# untitled.net
KiCad netlist of a schematic drawn in EAGLE
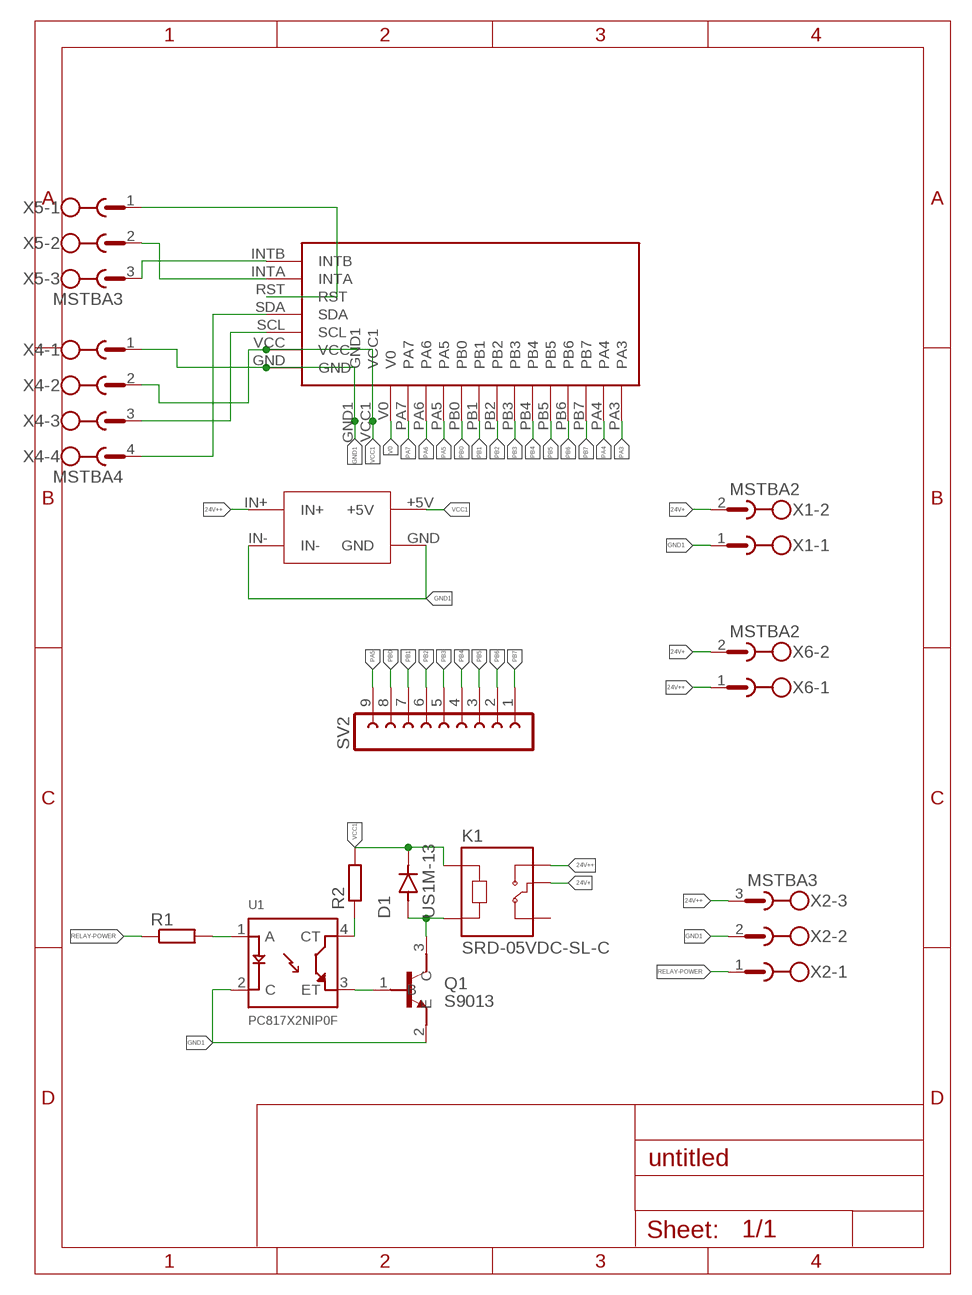
[diagram p0: schematic, sheet 1]

(export (version "E")
  (design (tool "Eeschema 10.0.6"))
  (components
    (comp (ref "D1")
      (value "US1M-13")
      (footprint "eagle-import:DIOM5226X240N")
      (fields (field (name "MF") "Diodes Incorporated"))
      (libsource (lib "eagle-import") (part "US1M-13"))
    )
    (comp (ref "K1")
      (value "SRD-05VDC-SL-C")
      (footprint "eagle-import:RELAY_SRD-05VDC-SL-C")
      (fields (field (name "MF") "Songle Relay"))
      (libsource (lib "eagle-import") (part "SRD-05VDC-SL-C"))
    )
    (comp (ref "MCP23017-I2C1")
      (value "MCP23017-I2C")
      (footprint "eagle-import:MCP23017-I2C")
      (libsource (lib "eagle-import") (part "MCP23017-I2C"))
    )
    (comp (ref "Q1")
      (value "S9013")
      (footprint "eagle-import:SOT95P240X120-3N")
      (fields (field (name "MF") "JCET"))
      (libsource (lib "eagle-import") (part "S9013"))
    )
    (comp (ref "R1")
      (value "R-EU_R0805")
      (footprint "eagle-import:R0805")
      (libsource (lib "eagle-import") (part "R-EU_R0805"))
    )
    (comp (ref "R2")
      (value "R-EU_R0805")
      (footprint "eagle-import:R0805")
      (libsource (lib "eagle-import") (part "R-EU_R0805"))
    )
    (comp (ref "SUPER-STEPDOWN1")
      (value "SUPER-STEPDOWN")
      (footprint "eagle-import:SUPER-STEPDOWN")
      (libsource (lib "eagle-import") (part "SUPER-STEPDOWN"))
    )
    (comp (ref "SV2")
      (value "FE09-1")
      (footprint "eagle-import:FE09")
      (libsource (lib "eagle-import") (part "FE09-1"))
    )
    (comp (ref "U1")
      (value "PC817X2NIP0F")
      (footprint "eagle-import:SOT254P975X400-4N")
      (fields (field (name "MF") "Sharp Microelectronics"))
      (libsource (lib "eagle-import") (part "PC817X2NIP0F"))
    )
    (comp (ref "X1")
      (value "MSTBA2")
      (footprint "eagle-import:MSTBA2")
      (fields (field (name "MF") "FARNELL") (field (name "MPN") "1757242"))
      (libsource (lib "eagle-import") (part "MSTBA2"))
    )
    (comp (ref "X2")
      (value "MSTBA3")
      (footprint "eagle-import:MSTBA3")
      (fields (field (name "MF") "FARNELL") (field (name "MPN") "1757255"))
      (libsource (lib "eagle-import") (part "MSTBA3"))
    )
    (comp (ref "X4")
      (value "MSTBA4")
      (footprint "eagle-import:MSTBA4")
      (fields (field (name "MF") "FARNELL") (field (name "MPN") "1757268"))
      (libsource (lib "eagle-import") (part "MSTBA4"))
    )
    (comp (ref "X5")
      (value "MSTBA3")
      (footprint "eagle-import:MSTBA3")
      (fields (field (name "MF") "FARNELL") (field (name "MPN") "1757255"))
      (libsource (lib "eagle-import") (part "MSTBA3"))
    )
    (comp (ref "X6")
      (value "MSTBA2")
      (footprint "eagle-import:MSTBA2")
      (fields (field (name "MF") "FARNELL") (field (name "MPN") "1757242"))
      (libsource (lib "eagle-import") (part "MSTBA2"))
    )
  )
  (nets
    (net (code "1") (name "24V+") (class "Default")
      (node (ref "K1") (pin "COM") (pinfunction "COM_COM") (pintype "passive"))
      (node (ref "X1") (pin "2") (pinfunction "1_2") (pintype "passive"))
      (node (ref "X6") (pin "2") (pinfunction "1_2") (pintype "passive"))
    )
    (net (code "2") (name "24V++") (class "Default")
      (node (ref "K1") (pin "NO") (pinfunction "NO_NO") (pintype "passive"))
      (node (ref "SUPER-STEPDOWN1") (pin "IN+") (pinfunction "IN+_IN+") (pintype "bidirectional"))
      (node (ref "X2") (pin "3") (pinfunction "1_3") (pintype "passive"))
      (node (ref "X6") (pin "1") (pinfunction "1_1") (pintype "passive"))
    )
    (net (code "3") (name "GND1") (class "Default")
      (node (ref "MCP23017-I2C1") (pin "GND") (pinfunction "GND_GND") (pintype "bidirectional"))
      (node (ref "MCP23017-I2C1") (pin "GND1") (pinfunction "GND1_GND1") (pintype "bidirectional"))
      (node (ref "Q1") (pin "2") (pinfunction "E_2") (pintype "passive"))
      (node (ref "SUPER-STEPDOWN1") (pin "GND") (pinfunction "GND_GND") (pintype "bidirectional"))
      (node (ref "SUPER-STEPDOWN1") (pin "IN-") (pinfunction "IN-_IN-") (pintype "bidirectional"))
      (node (ref "U1") (pin "2") (pinfunction "C_2") (pintype "passive"))
      (node (ref "X1") (pin "1") (pinfunction "1_1") (pintype "passive"))
      (node (ref "X2") (pin "2") (pinfunction "1_2") (pintype "passive"))
      (node (ref "X4") (pin "1") (pinfunction "1_1") (pintype "passive"))
    )
    (net (code "4") (name "Net-(MCP23017-I2C1-PadRST)") (class "Default")
      (node (ref "MCP23017-I2C1") (pin "RST") (pinfunction "RST_RST") (pintype "bidirectional"))
      (node (ref "X5") (pin "1") (pinfunction "1_1") (pintype "passive"))
    )
    (net (code "5") (name "Net-(Q1-B)") (class "Default")
      (node (ref "Q1") (pin "1") (pinfunction "B_1") (pintype "passive"))
      (node (ref "U1") (pin "3") (pinfunction "ET_3") (pintype "passive"))
    )
    (net (code "6") (name "Net-(Q1-C)") (class "Default")
      (node (ref "D1") (pin "A") (pinfunction "A_A") (pintype "passive"))
      (node (ref "K1") (pin "A2") (pinfunction "A2_A2") (pintype "passive"))
      (node (ref "Q1") (pin "3") (pinfunction "C_3") (pintype "passive"))
    )
    (net (code "7") (name "Net-(U1-A)") (class "Default")
      (node (ref "R1") (pin "2") (pinfunction "2_2") (pintype "passive"))
      (node (ref "U1") (pin "1") (pinfunction "A_1") (pintype "passive"))
    )
    (net (code "8") (name "Net-(U1-CT)") (class "Default")
      (node (ref "R2") (pin "1") (pinfunction "1_1") (pintype "passive"))
      (node (ref "U1") (pin "4") (pinfunction "CT_4") (pintype "passive"))
    )
    (net (code "9") (name "Net-(X4C-1)") (class "Default")
      (node (ref "MCP23017-I2C1") (pin "SCL") (pinfunction "SCL_SCL") (pintype "bidirectional"))
      (node (ref "X4") (pin "3") (pinfunction "1_3") (pintype "passive"))
    )
    (net (code "10") (name "Net-(X4D-1)") (class "Default")
      (node (ref "MCP23017-I2C1") (pin "SDA") (pinfunction "SDA_SDA") (pintype "bidirectional"))
      (node (ref "X4") (pin "4") (pinfunction "1_4") (pintype "passive"))
    )
    (net (code "11") (name "Net-(X5B-1)") (class "Default")
      (node (ref "MCP23017-I2C1") (pin "INTA") (pinfunction "INTA_INTA") (pintype "bidirectional"))
      (node (ref "X5") (pin "2") (pinfunction "1_2") (pintype "passive"))
    )
    (net (code "12") (name "Net-(X5C-1)") (class "Default")
      (node (ref "MCP23017-I2C1") (pin "INTB") (pinfunction "INTB_INTB") (pintype "bidirectional"))
      (node (ref "X5") (pin "3") (pinfunction "1_3") (pintype "passive"))
    )
    (net (code "13") (name "PA3") (class "Default")
      (node (ref "MCP23017-I2C1") (pin "PA3") (pinfunction "PA3_PA3") (pintype "bidirectional"))
    )
    (net (code "14") (name "PA4") (class "Default")
      (node (ref "MCP23017-I2C1") (pin "PA4") (pinfunction "PA4_PA4") (pintype "bidirectional"))
    )
    (net (code "15") (name "PA5") (class "Default")
      (node (ref "MCP23017-I2C1") (pin "PA5") (pinfunction "PA5_PA5") (pintype "bidirectional"))
      (node (ref "SV2") (pin "9") (pinfunction "9_9") (pintype "passive"))
    )
    (net (code "16") (name "PA6") (class "Default")
      (node (ref "MCP23017-I2C1") (pin "PA6") (pinfunction "PA6_PA6") (pintype "bidirectional"))
    )
    (net (code "17") (name "PA7") (class "Default")
      (node (ref "MCP23017-I2C1") (pin "PA7") (pinfunction "PA7_PA7") (pintype "bidirectional"))
    )
    (net (code "18") (name "PB0") (class "Default")
      (node (ref "MCP23017-I2C1") (pin "PB0") (pinfunction "PB0_PB0") (pintype "bidirectional"))
      (node (ref "SV2") (pin "8") (pinfunction "8_8") (pintype "passive"))
    )
    (net (code "19") (name "PB1") (class "Default")
      (node (ref "MCP23017-I2C1") (pin "PB1") (pinfunction "PB1_PB1") (pintype "bidirectional"))
      (node (ref "SV2") (pin "7") (pinfunction "7_7") (pintype "passive"))
    )
    (net (code "20") (name "PB2") (class "Default")
      (node (ref "MCP23017-I2C1") (pin "PB2") (pinfunction "PB2_PB2") (pintype "bidirectional"))
      (node (ref "SV2") (pin "6") (pinfunction "6_6") (pintype "passive"))
    )
    (net (code "21") (name "PB3") (class "Default")
      (node (ref "MCP23017-I2C1") (pin "PB3") (pinfunction "PB3_PB3") (pintype "bidirectional"))
      (node (ref "SV2") (pin "5") (pinfunction "5_5") (pintype "passive"))
    )
    (net (code "22") (name "PB4") (class "Default")
      (node (ref "MCP23017-I2C1") (pin "PB4") (pinfunction "PB4_PB4") (pintype "bidirectional"))
      (node (ref "SV2") (pin "4") (pinfunction "4_4") (pintype "passive"))
    )
    (net (code "23") (name "PB5") (class "Default")
      (node (ref "MCP23017-I2C1") (pin "PB5") (pinfunction "PB5_PB5") (pintype "bidirectional"))
      (node (ref "SV2") (pin "3") (pinfunction "3_3") (pintype "passive"))
    )
    (net (code "24") (name "PB6") (class "Default")
      (node (ref "MCP23017-I2C1") (pin "PB6") (pinfunction "PB6_PB6") (pintype "bidirectional"))
      (node (ref "SV2") (pin "2") (pinfunction "2_2") (pintype "passive"))
    )
    (net (code "25") (name "PB7") (class "Default")
      (node (ref "MCP23017-I2C1") (pin "PB7") (pinfunction "PB7_PB7") (pintype "bidirectional"))
      (node (ref "SV2") (pin "1") (pinfunction "1_1") (pintype "passive"))
    )
    (net (code "26") (name "RELAY-POWER") (class "Default")
      (node (ref "R1") (pin "1") (pinfunction "1_1") (pintype "passive"))
      (node (ref "X2") (pin "1") (pinfunction "1_1") (pintype "passive"))
    )
    (net (code "27") (name "V0") (class "Default")
      (node (ref "MCP23017-I2C1") (pin "V0") (pinfunction "V0_V0") (pintype "bidirectional"))
    )
    (net (code "28") (name "VCC1") (class "Default")
      (node (ref "D1") (pin "C") (pinfunction "K_C") (pintype "passive"))
      (node (ref "K1") (pin "A1") (pinfunction "A1_A1") (pintype "passive"))
      (node (ref "MCP23017-I2C1") (pin "VCC") (pinfunction "VCC_VCC") (pintype "bidirectional"))
      (node (ref "MCP23017-I2C1") (pin "VCC1") (pinfunction "VCC1_VCC1") (pintype "bidirectional"))
      (node (ref "R2") (pin "2") (pinfunction "2_2") (pintype "passive"))
      (node (ref "SUPER-STEPDOWN1") (pin "+5V") (pinfunction "+5V_+5V") (pintype "bidirectional"))
      (node (ref "X4") (pin "2") (pinfunction "1_2") (pintype "passive"))
    )
    (net (code "29") (name "unconnected-(K1-PadNC)") (class "Default")
      (node (ref "K1") (pin "NC") (pinfunction "NC_NC") (pintype "passive"))
    )
  )
)
